# RF.net
KiCad netlist of a schematic drawn in Altium Designer
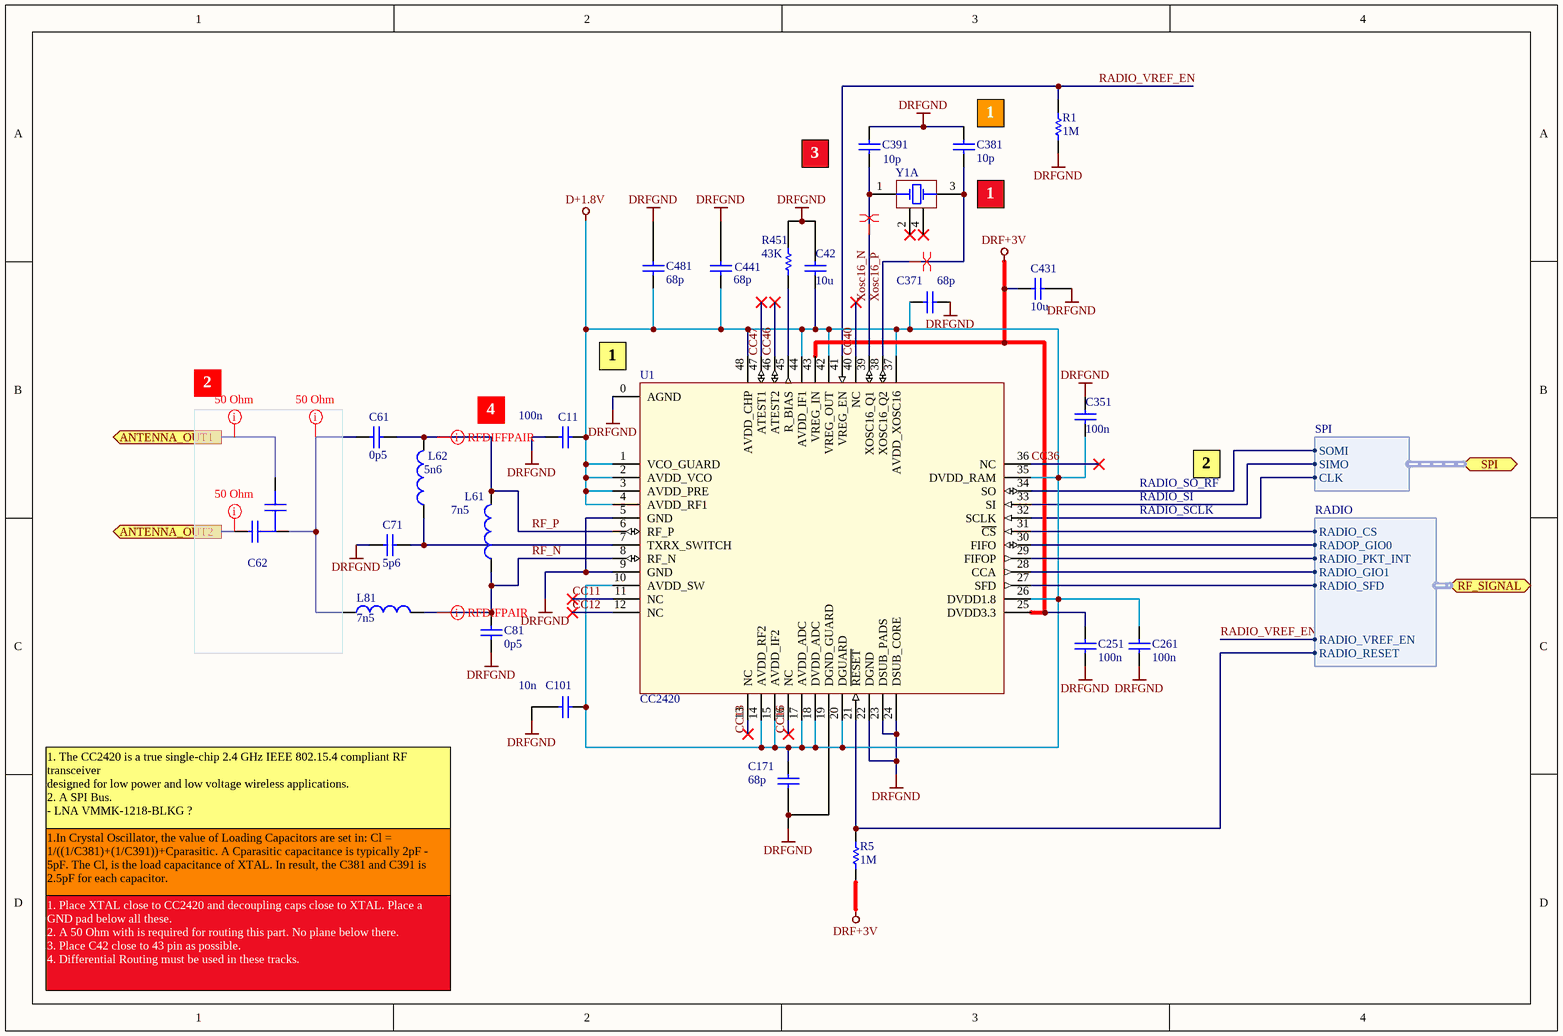
[diagram p0: RF.SchDoc]

(export (version "E")
  (design (tool "Eeschema 10.0.6"))
  (components
    (comp (ref "C11")
      (value "100n")
      (footprint "CC-0402-AL")
      (description "Capacitor (Semiconductor SIM Model)")
      (fields (field (name "Comment") "Cap Semi"))
      (libsource (lib "Z1_Project") (part "Cap Semi"))
    )
    (comp (ref "C42")
      (value "10u")
      (footprint "CC2013-0805")
      (description "Capacitor (Semiconductor SIM Model)")
      (fields (field (name "Comment") "Cap Semi"))
      (libsource (lib "Z1_Project") (part "Cap Semi"))
    )
    (comp (ref "C61")
      (value "0p5")
      (footprint "CC-0402-AL")
      (description "Capacitor (Semiconductor SIM Model)")
      (fields (field (name "Comment") "Cap Semi"))
      (libsource (lib "Z1_Project") (part "Cap Semi"))
    )
    (comp (ref "C62")
      (value "Bilateral Switch Capacitor")
      (footprint "Dual Capacitor Switch")
      (libsource (lib "Z1_Project") (part "Bilateral Switch Capacitor"))
    )
    (comp (ref "C71")
      (value "5p6")
      (footprint "CC-0402-AL")
      (description "Capacitor (Semiconductor SIM Model)")
      (fields (field (name "Comment") "Cap Semi"))
      (libsource (lib "Z1_Project") (part "Cap Semi"))
    )
    (comp (ref "C81")
      (value "0p5")
      (footprint "CC-0402-AL")
      (description "Capacitor (Semiconductor SIM Model)")
      (fields (field (name "Comment") "Cap Semi"))
      (libsource (lib "Z1_Project") (part "Cap Semi"))
    )
    (comp (ref "C101")
      (value "10n")
      (footprint "CC-0402-AL")
      (description "Capacitor (Semiconductor SIM Model)")
      (fields (field (name "Comment") "Cap Semi"))
      (libsource (lib "Z1_Project") (part "Cap Semi"))
    )
    (comp (ref "C171")
      (value "68p")
      (footprint "CC-0402-AL")
      (description "Capacitor (Semiconductor SIM Model)")
      (fields (field (name "Comment") "Cap Semi"))
      (libsource (lib "Z1_Project") (part "Cap Semi"))
    )
    (comp (ref "C251")
      (value "100n")
      (footprint "CC-0402-AL")
      (description "Capacitor (Semiconductor SIM Model)")
      (fields (field (name "Comment") "Cap Semi"))
      (libsource (lib "Z1_Project") (part "Cap Semi"))
    )
    (comp (ref "C261")
      (value "100n")
      (footprint "CC-0402-AL")
      (description "Capacitor (Semiconductor SIM Model)")
      (fields (field (name "Comment") "Cap Semi"))
      (libsource (lib "Z1_Project") (part "Cap Semi"))
    )
    (comp (ref "C351")
      (value "100n")
      (footprint "CC-0402-AL")
      (description "Capacitor (Semiconductor SIM Model)")
      (fields (field (name "Comment") "Cap Semi"))
      (libsource (lib "Z1_Project") (part "Cap Semi"))
    )
    (comp (ref "C371")
      (value "68p")
      (footprint "CC-0402-AL")
      (description "Capacitor (Semiconductor SIM Model)")
      (fields (field (name "Comment") "Cap Semi"))
      (libsource (lib "Z1_Project") (part "Cap Semi"))
    )
    (comp (ref "C381")
      (value "10p")
      (footprint "CC-0402-AL")
      (description "Capacitor (Semiconductor SIM Model)")
      (fields (field (name "Comment") "Cap Semi"))
      (libsource (lib "Z1_Project") (part "Cap Semi"))
    )
    (comp (ref "C391")
      (value "10p")
      (footprint "CC-0402-AL")
      (description "Capacitor (Semiconductor SIM Model)")
      (fields (field (name "Comment") "Cap Semi"))
      (libsource (lib "Z1_Project") (part "Cap Semi"))
    )
    (comp (ref "C431")
      (value "10u")
      (footprint "CC2013-0805")
      (description "Capacitor (Semiconductor SIM Model)")
      (fields (field (name "Comment") "Cap Semi"))
      (libsource (lib "Z1_Project") (part "Cap Semi"))
    )
    (comp (ref "C441")
      (value "68p")
      (footprint "CC-0402-AL")
      (description "Capacitor (Semiconductor SIM Model)")
      (fields (field (name "Comment") "Cap Semi"))
      (libsource (lib "Z1_Project") (part "Cap Semi"))
    )
    (comp (ref "C481")
      (value "68p")
      (footprint "CC-0402-AL")
      (description "Capacitor (Semiconductor SIM Model)")
      (fields (field (name "Comment") "Cap Semi"))
      (libsource (lib "Z1_Project") (part "Cap Semi"))
    )
    (comp (ref "L61")
      (value "7n5")
      (footprint "INDC1005-0402-ALT")
      (description "Inductor")
      (libsource (lib "Z1_Project") (part "Inductor"))
    )
    (comp (ref "L62")
      (value "5n6")
      (footprint "INDC1005-0402")
      (description "Inductor")
      (libsource (lib "Z1_Project") (part "Inductor"))
    )
    (comp (ref "L81")
      (value "7n5")
      (footprint "INDC1005-0402")
      (description "Inductor")
      (libsource (lib "Z1_Project") (part "Inductor"))
    )
    (comp (ref "R1")
      (value "1M")
      (footprint "CR-0402-AL")
      (description "Semiconductor Resistor")
      (fields (field (name "MANUFACTURER") "Generic Components") (field (name "Comment") "Res Semi"))
      (libsource (lib "Z1_Project") (part "Res Semi"))
    )
    (comp (ref "R5")
      (value "1M")
      (footprint "CR-0402-AL")
      (description "Semiconductor Resistor")
      (fields (field (name "MANUFACTURER") "Generic Components") (field (name "Comment") "Res Semi"))
      (libsource (lib "Z1_Project") (part "Res Semi"))
    )
    (comp (ref "R451")
      (value "43K")
      (footprint "CR-0402-AL")
      (description "RES 43.0K OHM 1/16W 1% 0402 SMD")
      (fields (field (name "MANUFACTURER") "Generic Components") (field (name "Comment") "Res Semi"))
      (libsource (lib "Z1_Project") (part "Res Semi"))
    )
    (comp (ref "U1")
      (value "CC2420")
      (footprint "QFN7X7-48")
      (description "2.4 GHz IEEE 802.15.4 / ZigBee-ready RF Transceiver")
      (libsource (lib "Z1_Project") (part "CC2420"))
    )
    (comp (ref "Y1")
      (value "XTAL 4pins")
      (footprint "NX3225SA- 16.000000Hhz-B3")
      (description "XTAL 7.2pF Load Capacitance.")
      (fields (field (name "MANUFACTURER") "Generic Components"))
      (libsource (lib "Z1_Project") (part "XTAL 4pins"))
    )
  )
  (nets
    (net (code "3") (name "/ANTENNA_OUT1") (class "Default")
      (node (ref "C62") (pin "3") (pinfunction "3_3") (pintype "passive"))
    )
    (net (code "4") (name "/ANTENNA_OUT2") (class "Default")
      (node (ref "C62") (pin "2") (pinfunction "2_2") (pintype "passive"))
    )
    (net (code "5") (name "/CC11") (class "Default")
      (node (ref "U1") (pin "11") (pinfunction "NC_11") (pintype "passive+no_connect"))
    )
    (net (code "6") (name "/CC12") (class "Default")
      (node (ref "U1") (pin "12") (pinfunction "NC_12") (pintype "passive+no_connect"))
    )
    (net (code "7") (name "/CC13") (class "Default")
      (node (ref "U1") (pin "13") (pinfunction "NC_13") (pintype "passive+no_connect"))
    )
    (net (code "8") (name "/CC16") (class "Default")
      (node (ref "U1") (pin "16") (pinfunction "NC_16") (pintype "passive+no_connect"))
    )
    (net (code "9") (name "/CC36") (class "Default")
      (node (ref "U1") (pin "36") (pinfunction "NC_36") (pintype "passive+no_connect"))
    )
    (net (code "10") (name "/CC40") (class "Default")
      (node (ref "U1") (pin "40") (pinfunction "NC_40") (pintype "power_in+no_connect"))
    )
    (net (code "11") (name "/CC46") (class "Default")
      (node (ref "U1") (pin "46") (pinfunction "ATEST2_46") (pintype "bidirectional+no_connect"))
    )
    (net (code "12") (name "/CC47") (class "Default")
      (node (ref "U1") (pin "47") (pinfunction "ATEST1_47") (pintype "bidirectional+no_connect"))
    )
    (net (code "13") (name "/CLK") (class "Default")
      (node (ref "U1") (pin "32") (pinfunction "SCLK_32") (pintype "input"))
    )
    (net (code "14") (name "/RADIO_CS") (class "Default")
      (node (ref "U1") (pin "31") (pinfunction "~{CS}_31") (pintype "input"))
    )
    (net (code "15") (name "/RADIO_GIO1") (class "Default")
      (node (ref "U1") (pin "28") (pinfunction "CCA_28") (pintype "output"))
    )
    (net (code "16") (name "/RADIO_PKT_INT") (class "Default")
      (node (ref "U1") (pin "29") (pinfunction "FIFOP_29") (pintype "output"))
    )
    (net (code "17") (name "/RADIO_RESET") (class "Default")
      (node (ref "R5") (pin "2") (pinfunction "2_2") (pintype "passive"))
      (node (ref "U1") (pin "21") (pinfunction "~{RESET}_21") (pintype "input"))
    )
    (net (code "18") (name "/RADIO_SFD") (class "Default")
      (node (ref "U1") (pin "27") (pinfunction "SFD_27") (pintype "output"))
    )
    (net (code "19") (name "/RADIO_VREF_EN") (class "Default")
      (node (ref "R1") (pin "2") (pinfunction "2_2") (pintype "passive"))
      (node (ref "U1") (pin "41") (pinfunction "VREG_EN_41") (pintype "input"))
    )
    (net (code "20") (name "/RADOP_GIO0") (class "Default")
      (node (ref "U1") (pin "30") (pinfunction "FIFO_30") (pintype "bidirectional"))
    )
    (net (code "21") (name "/RF_N") (class "Default")
      (node (ref "C81") (pin "2") (pinfunction "2_2") (pintype "passive"))
      (node (ref "L61") (pin "1") (pinfunction "1_1") (pintype "passive"))
      (node (ref "L81") (pin "2") (pinfunction "2_2") (pintype "passive"))
      (node (ref "U1") (pin "8") (pinfunction "RF_N_8") (pintype "bidirectional"))
    )
    (net (code "22") (name "/RF_P") (class "Default")
      (node (ref "C61") (pin "1") (pinfunction "1_1") (pintype "passive"))
      (node (ref "L61") (pin "2") (pinfunction "2_2") (pintype "passive"))
      (node (ref "L62") (pin "2") (pinfunction "2_2") (pintype "passive"))
      (node (ref "U1") (pin "6") (pinfunction "RF_P_6") (pintype "bidirectional"))
    )
    (net (code "23") (name "/SIMO") (class "Default")
      (node (ref "U1") (pin "33") (pinfunction "SI_33") (pintype "input"))
    )
    (net (code "24") (name "/SOMI") (class "Default")
      (node (ref "U1") (pin "34") (pinfunction "SO_34") (pintype "bidirectional"))
    )
    (net (code "25") (name "/Xosc16_N") (class "Default")
      (node (ref "C391") (pin "1") (pinfunction "1_1") (pintype "passive"))
      (node (ref "U1") (pin "39") (pinfunction "XOSC16_Q1_39") (pintype "bidirectional"))
      (node (ref "Y1") (pin "1") (pinfunction "OSC1_1") (pintype "passive"))
    )
    (net (code "26") (name "/Xosc16_P") (class "Default")
      (node (ref "C381") (pin "1") (pinfunction "1_1") (pintype "passive"))
      (node (ref "U1") (pin "38") (pinfunction "XOSC16_Q2_38") (pintype "bidirectional"))
      (node (ref "Y1") (pin "3") (pinfunction "OSC2_3") (pintype "passive"))
    )
    (net (code "29") (name "D+1.8V") (class "Default")
      (node (ref "C101") (pin "2") (pinfunction "2_2") (pintype "passive"))
      (node (ref "C11") (pin "2") (pinfunction "2_2") (pintype "passive"))
      (node (ref "C171") (pin "1") (pinfunction "1_1") (pintype "passive"))
      (node (ref "C261") (pin "1") (pinfunction "1_1") (pintype "passive"))
      (node (ref "C351") (pin "1") (pinfunction "1_1") (pintype "passive"))
      (node (ref "C371") (pin "1") (pinfunction "1_1") (pintype "passive"))
      (node (ref "C42") (pin "1") (pinfunction "1_1") (pintype "passive"))
      (node (ref "C441") (pin "1") (pinfunction "1_1") (pintype "passive"))
      (node (ref "C481") (pin "1") (pinfunction "1_1") (pintype "passive"))
      (node (ref "U1") (pin "1") (pinfunction "VCO_GUARD_1") (pintype "power_in"))
      (node (ref "U1") (pin "10") (pinfunction "AVDD_SW_10") (pintype "power_in"))
      (node (ref "U1") (pin "14") (pinfunction "AVDD_RF2_14") (pintype "power_in"))
      (node (ref "U1") (pin "15") (pinfunction "AVDD_IF2_15") (pintype "power_in"))
      (node (ref "U1") (pin "17") (pinfunction "AVDD_ADC_17") (pintype "power_in"))
      (node (ref "U1") (pin "18") (pinfunction "DVDD_ADC_18") (pintype "power_in"))
      (node (ref "U1") (pin "2") (pinfunction "AVDD_VCO_2") (pintype "power_in"))
      (node (ref "U1") (pin "20") (pinfunction "DGUARD_20") (pintype "power_in"))
      (node (ref "U1") (pin "26") (pinfunction "DVDD1.8_26") (pintype "power_in"))
      (node (ref "U1") (pin "3") (pinfunction "AVDD_PRE_3") (pintype "power_in"))
      (node (ref "U1") (pin "35") (pinfunction "DVDD_RAM_35") (pintype "power_in"))
      (node (ref "U1") (pin "37") (pinfunction "AVDD_XOSC16_37") (pintype "power_in"))
      (node (ref "U1") (pin "4") (pinfunction "AVDD_RF1_4") (pintype "power_in"))
      (node (ref "U1") (pin "42") (pinfunction "VREG_OUT_42") (pintype "power_in"))
      (node (ref "U1") (pin "44") (pinfunction "AVDD_IF1_44") (pintype "power_in"))
      (node (ref "U1") (pin "48") (pinfunction "AVDD_CHP_48") (pintype "power_in"))
    )
    (net (code "30") (name "DRF+3V") (class "Default")
      (node (ref "C251") (pin "1") (pinfunction "1_1") (pintype "passive"))
      (node (ref "C431") (pin "2") (pinfunction "2_2") (pintype "passive"))
      (node (ref "R5") (pin "1") (pinfunction "1_1") (pintype "passive"))
      (node (ref "U1") (pin "25") (pinfunction "DVDD3.3_25") (pintype "power_in"))
      (node (ref "U1") (pin "43") (pinfunction "VREG_IN_43") (pintype "power_in"))
    )
    (net (code "31") (name "DRFGND") (class "Default")
      (node (ref "C101") (pin "1") (pinfunction "1_1") (pintype "passive"))
      (node (ref "C11") (pin "1") (pinfunction "1_1") (pintype "passive"))
      (node (ref "C171") (pin "2") (pinfunction "2_2") (pintype "passive"))
      (node (ref "C251") (pin "2") (pinfunction "2_2") (pintype "passive"))
      (node (ref "C261") (pin "2") (pinfunction "2_2") (pintype "passive"))
      (node (ref "C351") (pin "2") (pinfunction "2_2") (pintype "passive"))
      (node (ref "C371") (pin "2") (pinfunction "2_2") (pintype "passive"))
      (node (ref "C381") (pin "2") (pinfunction "2_2") (pintype "passive"))
      (node (ref "C391") (pin "2") (pinfunction "2_2") (pintype "passive"))
      (node (ref "C42") (pin "2") (pinfunction "2_2") (pintype "passive"))
      (node (ref "C431") (pin "1") (pinfunction "1_1") (pintype "passive"))
      (node (ref "C441") (pin "2") (pinfunction "2_2") (pintype "passive"))
      (node (ref "C481") (pin "2") (pinfunction "2_2") (pintype "passive"))
      (node (ref "C71") (pin "2") (pinfunction "2_2") (pintype "passive"))
      (node (ref "C81") (pin "1") (pinfunction "1_1") (pintype "passive"))
      (node (ref "R1") (pin "1") (pinfunction "1_1") (pintype "passive"))
      (node (ref "R451") (pin "2") (pinfunction "2_2") (pintype "passive"))
      (node (ref "U1") (pin "0") (pinfunction "AGND_0") (pintype "power_in"))
      (node (ref "U1") (pin "19") (pinfunction "DGND_GUARD_19") (pintype "power_in"))
      (node (ref "U1") (pin "22") (pinfunction "DGND_22") (pintype "power_in"))
      (node (ref "U1") (pin "23") (pinfunction "DSUB_PADS_23") (pintype "power_in"))
      (node (ref "U1") (pin "24") (pinfunction "DSUB_CORE_24") (pintype "power_in"))
      (node (ref "U1") (pin "5") (pinfunction "GND_5") (pintype "power_in"))
      (node (ref "U1") (pin "9") (pinfunction "GND_9") (pintype "power_in"))
    )
    (net (code "32") (name "Net-(C61-Pad2)") (class "Default")
      (node (ref "C61") (pin "2") (pinfunction "2_2") (pintype "passive"))
      (node (ref "C62") (pin "1") (pinfunction "1_1") (pintype "passive"))
      (node (ref "L81") (pin "1") (pinfunction "1_1") (pintype "passive"))
    )
    (net (code "33") (name "Net-(U1-R_BIAS)") (class "Default")
      (node (ref "R451") (pin "1") (pinfunction "1_1") (pintype "passive"))
      (node (ref "U1") (pin "45") (pinfunction "R_BIAS_45") (pintype "output"))
    )
    (net (code "34") (name "Net-(U1-TXRX_SWITCH)") (class "Default")
      (node (ref "C71") (pin "1") (pinfunction "1_1") (pintype "passive"))
      (node (ref "L62") (pin "1") (pinfunction "1_1") (pintype "passive"))
      (node (ref "U1") (pin "7") (pinfunction "TXRX_SWITCH_7") (pintype "power_in"))
    )
    (net (code "35") (name "unconnected-(Y1-GND-Pad2)") (class "Default")
      (node (ref "Y1") (pin "2") (pinfunction "GND_2") (pintype "passive+no_connect"))
    )
    (net (code "36") (name "unconnected-(Y1-GND-Pad4)") (class "Default")
      (node (ref "Y1") (pin "4") (pinfunction "GND_4") (pintype "passive+no_connect"))
    )
  )
)
